# octave-fuzz.net
KiCad netlist of a schematic drawn in EAGLE
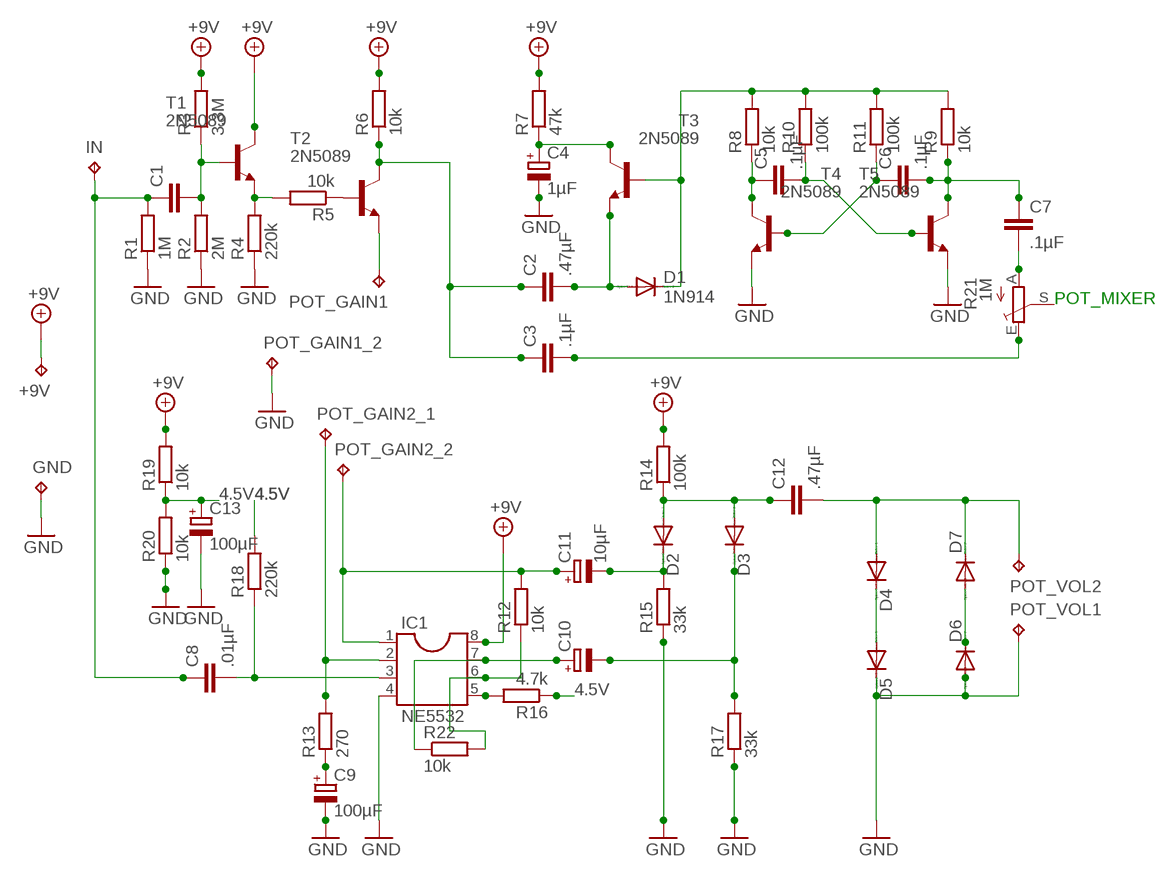
[diagram p0: schematic, sheet 1]

(export (version "E")
  (design (tool "Eeschema 10.0.6"))
  (components
    (comp (ref "+9V")
      (value "TPPAD1-20Y")
      (footprint "eagle-import:P1-20Y")
      (libsource (lib "eagle-import") (part "TPPAD1-20Y"))
    )
    (comp (ref "C1")
      (value "C-EU050-025X075")
      (footprint "eagle-import:C050-025X075")
      (libsource (lib "eagle-import") (part "C-EU050-025X075"))
    )
    (comp (ref "C2")
      (value ".47µF")
      (footprint "eagle-import:C050-025X075")
      (libsource (lib "eagle-import") (part "C-EU050-025X075"))
    )
    (comp (ref "C3")
      (value ".1µF")
      (footprint "eagle-import:C050-025X075")
      (libsource (lib "eagle-import") (part "C-EU050-025X075"))
    )
    (comp (ref "C4")
      (value "1µF")
      (footprint "eagle-import:E3,5-8")
      (libsource (lib "eagle-import") (part "CPOL-EUE3.5-8"))
    )
    (comp (ref "C5")
      (value ".1µF")
      (footprint "eagle-import:C050-025X075")
      (libsource (lib "eagle-import") (part "C-EU050-025X075"))
    )
    (comp (ref "C6")
      (value ".1µF")
      (footprint "eagle-import:C050-025X075")
      (libsource (lib "eagle-import") (part "C-EU050-025X075"))
    )
    (comp (ref "C7")
      (value ".1µF")
      (footprint "eagle-import:C050-025X075")
      (libsource (lib "eagle-import") (part "C-EU050-025X075"))
    )
    (comp (ref "C8")
      (value ".01µF")
      (footprint "eagle-import:C050-025X075")
      (libsource (lib "eagle-import") (part "C-EU050-025X075"))
    )
    (comp (ref "C9")
      (value "100µF")
      (footprint "eagle-import:E3,5-8")
      (libsource (lib "eagle-import") (part "CPOL-EUE3.5-8"))
    )
    (comp (ref "C10")
      (value "CPOL-EUE3.5-8")
      (footprint "eagle-import:E3,5-8")
      (libsource (lib "eagle-import") (part "CPOL-EUE3.5-8"))
    )
    (comp (ref "C11")
      (value "10µF")
      (footprint "eagle-import:E3,5-8")
      (libsource (lib "eagle-import") (part "CPOL-EUE3.5-8"))
    )
    (comp (ref "C12")
      (value ".47µF")
      (footprint "eagle-import:C050-025X075")
      (libsource (lib "eagle-import") (part "C-EU050-025X075"))
    )
    (comp (ref "C13")
      (value "100µF")
      (footprint "eagle-import:E3,5-8")
      (libsource (lib "eagle-import") (part "CPOL-EUE3.5-8"))
    )
    (comp (ref "D1")
      (value "1N914")
      (footprint "eagle-import:D-12.5")
      (libsource (lib "eagle-import") (part "DIODE-D-12.5"))
    )
    (comp (ref "D2")
      (value "DIODE-D-12.5")
      (footprint "eagle-import:D-12.5")
      (libsource (lib "eagle-import") (part "DIODE-D-12.5"))
    )
    (comp (ref "D3")
      (value "DIODE-D-12.5")
      (footprint "eagle-import:D-12.5")
      (libsource (lib "eagle-import") (part "DIODE-D-12.5"))
    )
    (comp (ref "D4")
      (value "DIODE-D-12.5")
      (footprint "eagle-import:D-12.5")
      (libsource (lib "eagle-import") (part "DIODE-D-12.5"))
    )
    (comp (ref "D5")
      (value "DIODE-D-12.5")
      (footprint "eagle-import:D-12.5")
      (libsource (lib "eagle-import") (part "DIODE-D-12.5"))
    )
    (comp (ref "D6")
      (value "DIODE-D-12.5")
      (footprint "eagle-import:D-12.5")
      (libsource (lib "eagle-import") (part "DIODE-D-12.5"))
    )
    (comp (ref "D7")
      (value "DIODE-D-12.5")
      (footprint "eagle-import:D-12.5")
      (libsource (lib "eagle-import") (part "DIODE-D-12.5"))
    )
    (comp (ref "GND")
      (value "TPPAD1-20Y")
      (footprint "eagle-import:P1-20Y")
      (libsource (lib "eagle-import") (part "TPPAD1-20Y"))
    )
    (comp (ref "IC1")
      (value "NE5532")
      (footprint "eagle-import:DIL08")
      (libsource (lib "eagle-import") (part "DIL8"))
    )
    (comp (ref "IN")
      (value "TPPAD1-17Y")
      (footprint "eagle-import:P1-17Y")
      (libsource (lib "eagle-import") (part "TPPAD1-17Y"))
    )
    (comp (ref "POT_GAIN1")
      (value "TPPAD1-20Y")
      (footprint "eagle-import:P1-20Y")
      (libsource (lib "eagle-import") (part "TPPAD1-20Y"))
    )
    (comp (ref "POT_GAIN1_2")
      (value "TPPAD1-20Y")
      (footprint "eagle-import:P1-20Y")
      (libsource (lib "eagle-import") (part "TPPAD1-20Y"))
    )
    (comp (ref "POT_GAIN2_1")
      (value "TPPAD1-20Y")
      (footprint "eagle-import:P1-20Y")
      (libsource (lib "eagle-import") (part "TPPAD1-20Y"))
    )
    (comp (ref "POT_GAIN2_2")
      (value "TPPAD1-20Y")
      (footprint "eagle-import:P1-20Y")
      (libsource (lib "eagle-import") (part "TPPAD1-20Y"))
    )
    (comp (ref "POT_VOL1")
      (value "TPPAD1-20Y")
      (footprint "eagle-import:P1-20Y")
      (libsource (lib "eagle-import") (part "TPPAD1-20Y"))
    )
    (comp (ref "POT_VOL2")
      (value "TPPAD1-20Y")
      (footprint "eagle-import:P1-20Y")
      (libsource (lib "eagle-import") (part "TPPAD1-20Y"))
    )
    (comp (ref "R1")
      (value "1M")
      (footprint "eagle-import:0207_10")
      (libsource (lib "eagle-import") (part "R-EU_0207/10"))
    )
    (comp (ref "R2")
      (value "2M")
      (footprint "eagle-import:0207_10")
      (libsource (lib "eagle-import") (part "R-EU_0207/10"))
    )
    (comp (ref "R3")
      (value "3.3M")
      (footprint "eagle-import:0207_10")
      (libsource (lib "eagle-import") (part "R-EU_0207/10"))
    )
    (comp (ref "R4")
      (value "220k")
      (footprint "eagle-import:0207_10")
      (libsource (lib "eagle-import") (part "R-EU_0207/10"))
    )
    (comp (ref "R5")
      (value "10k")
      (footprint "eagle-import:0207_10")
      (libsource (lib "eagle-import") (part "R-EU_0207/10"))
    )
    (comp (ref "R6")
      (value "10k")
      (footprint "eagle-import:0207_10")
      (libsource (lib "eagle-import") (part "R-EU_0207/10"))
    )
    (comp (ref "R7")
      (value "47k")
      (footprint "eagle-import:0207_10")
      (libsource (lib "eagle-import") (part "R-EU_0207/10"))
    )
    (comp (ref "R8")
      (value "10k")
      (footprint "eagle-import:0207_10")
      (libsource (lib "eagle-import") (part "R-EU_0207/10"))
    )
    (comp (ref "R9")
      (value "10k")
      (footprint "eagle-import:0207_10")
      (libsource (lib "eagle-import") (part "R-EU_0207/10"))
    )
    (comp (ref "R10")
      (value "100k")
      (footprint "eagle-import:0207_10")
      (libsource (lib "eagle-import") (part "R-EU_0207/10"))
    )
    (comp (ref "R11")
      (value "100k")
      (footprint "eagle-import:0207_10")
      (libsource (lib "eagle-import") (part "R-EU_0207/10"))
    )
    (comp (ref "R12")
      (value "10k")
      (footprint "eagle-import:0207_10")
      (libsource (lib "eagle-import") (part "R-EU_0207/10"))
    )
    (comp (ref "R13")
      (value "270")
      (footprint "eagle-import:0207_10")
      (libsource (lib "eagle-import") (part "R-EU_0207/10"))
    )
    (comp (ref "R14")
      (value "100k")
      (footprint "eagle-import:0207_10")
      (libsource (lib "eagle-import") (part "R-EU_0207/10"))
    )
    (comp (ref "R15")
      (value "33k")
      (footprint "eagle-import:0207_10")
      (libsource (lib "eagle-import") (part "R-EU_0207/10"))
    )
    (comp (ref "R16")
      (value "4.7k")
      (footprint "eagle-import:0207_10")
      (libsource (lib "eagle-import") (part "R-EU_0207/10"))
    )
    (comp (ref "R17")
      (value "33k")
      (footprint "eagle-import:0207_10")
      (libsource (lib "eagle-import") (part "R-EU_0207/10"))
    )
    (comp (ref "R18")
      (value "220k")
      (footprint "eagle-import:0207_10")
      (libsource (lib "eagle-import") (part "R-EU_0207/10"))
    )
    (comp (ref "R19")
      (value "10k")
      (footprint "eagle-import:0207_10")
      (libsource (lib "eagle-import") (part "R-EU_0207/10"))
    )
    (comp (ref "R20")
      (value "10k")
      (footprint "eagle-import:0207_10")
      (libsource (lib "eagle-import") (part "R-EU_0207/10"))
    )
    (comp (ref "R21")
      (value "1M")
      (footprint "eagle-import:CA9V")
      (libsource (lib "eagle-import") (part "TRIM_EU-CA9V"))
    )
    (comp (ref "R22")
      (value "10k")
      (footprint "eagle-import:0207_10")
      (libsource (lib "eagle-import") (part "R-EU_0207/10"))
    )
    (comp (ref "T1")
      (value "2N5089")
      (footprint "eagle-import:TO92")
      (libsource (lib "eagle-import") (part "2N5089"))
    )
    (comp (ref "T2")
      (value "2N5089")
      (footprint "eagle-import:TO92")
      (libsource (lib "eagle-import") (part "2N5089"))
    )
    (comp (ref "T3")
      (value "2N5089")
      (footprint "eagle-import:TO92")
      (libsource (lib "eagle-import") (part "2N5089"))
    )
    (comp (ref "T4")
      (value "2N5089")
      (footprint "eagle-import:TO92")
      (libsource (lib "eagle-import") (part "2N5089"))
    )
    (comp (ref "T5")
      (value "2N5089")
      (footprint "eagle-import:TO92")
      (libsource (lib "eagle-import") (part "2N5089"))
    )
  )
  (nets
    (net (code "1") (name "+9V") (class "Default")
      (node (ref "+9V") (pin "TP") (pinfunction "TP_TP") (pintype "input"))
      (node (ref "IC1") (pin "8") (pinfunction "8_8") (pintype "passive"))
      (node (ref "R14") (pin "2") (pinfunction "2_2") (pintype "passive"))
      (node (ref "R19") (pin "2") (pinfunction "2_2") (pintype "passive"))
      (node (ref "R3") (pin "2") (pinfunction "2_2") (pintype "passive"))
      (node (ref "R6") (pin "2") (pinfunction "2_2") (pintype "passive"))
      (node (ref "R7") (pin "2") (pinfunction "2_2") (pintype "passive"))
      (node (ref "T1") (pin "1") (pinfunction "C_1") (pintype "passive"))
    )
    (net (code "2") (name "/4.5V") (class "Default")
      (node (ref "C13") (pin "+") (pinfunction "+_+") (pintype "passive"))
      (node (ref "R16") (pin "1") (pinfunction "1_1") (pintype "passive"))
      (node (ref "R18") (pin "2") (pinfunction "2_2") (pintype "passive"))
      (node (ref "R19") (pin "1") (pinfunction "1_1") (pintype "passive"))
      (node (ref "R20") (pin "2") (pinfunction "2_2") (pintype "passive"))
    )
    (net (code "3") (name "GND") (class "Default")
      (node (ref "C13") (pin "-") (pinfunction "-_-") (pintype "passive"))
      (node (ref "C4") (pin "-") (pinfunction "-_-") (pintype "passive"))
      (node (ref "C9") (pin "-") (pinfunction "-_-") (pintype "passive"))
      (node (ref "D5") (pin "C") (pinfunction "C_C") (pintype "passive"))
      (node (ref "D6") (pin "A") (pinfunction "A_A") (pintype "passive"))
      (node (ref "GND") (pin "TP") (pinfunction "TP_TP") (pintype "input"))
      (node (ref "IC1") (pin "4") (pinfunction "4_4") (pintype "passive"))
      (node (ref "POT_GAIN1_2") (pin "TP") (pinfunction "TP_TP") (pintype "input"))
      (node (ref "POT_VOL1") (pin "TP") (pinfunction "TP_TP") (pintype "input"))
      (node (ref "R1") (pin "1") (pinfunction "1_1") (pintype "passive"))
      (node (ref "R15") (pin "1") (pinfunction "1_1") (pintype "passive"))
      (node (ref "R17") (pin "1") (pinfunction "1_1") (pintype "passive"))
      (node (ref "R2") (pin "1") (pinfunction "1_1") (pintype "passive"))
      (node (ref "R20") (pin "1") (pinfunction "1_1") (pintype "passive"))
      (node (ref "R4") (pin "1") (pinfunction "1_1") (pintype "passive"))
      (node (ref "T4") (pin "3") (pinfunction "E_3") (pintype "passive"))
      (node (ref "T5") (pin "3") (pinfunction "E_3") (pintype "passive"))
    )
    (net (code "4") (name "Net-(C1-Pad1)") (class "Default")
      (node (ref "C1") (pin "1") (pinfunction "1_1") (pintype "passive"))
      (node (ref "C8") (pin "1") (pinfunction "1_1") (pintype "passive"))
      (node (ref "IN") (pin "TP") (pinfunction "TP_TP") (pintype "input"))
      (node (ref "R1") (pin "2") (pinfunction "2_2") (pintype "passive"))
    )
    (net (code "5") (name "Net-(C3-Pad2)") (class "Default")
      (node (ref "C3") (pin "2") (pinfunction "2_2") (pintype "passive"))
      (node (ref "R21") (pin "E") (pinfunction "E_E") (pintype "passive"))
    )
    (net (code "6") (name "Net-(C7-Pad2)") (class "Default")
      (node (ref "C7") (pin "2") (pinfunction "2_2") (pintype "passive"))
      (node (ref "R21") (pin "A") (pinfunction "A_A") (pintype "passive"))
    )
    (net (code "7") (name "Net-(C8-Pad2)") (class "Default")
      (node (ref "C8") (pin "2") (pinfunction "2_2") (pintype "passive"))
      (node (ref "IC1") (pin "3") (pinfunction "3_3") (pintype "passive"))
      (node (ref "R18") (pin "1") (pinfunction "1_1") (pintype "passive"))
    )
    (net (code "8") (name "Net-(C9-Pad+)") (class "Default")
      (node (ref "C9") (pin "+") (pinfunction "+_+") (pintype "passive"))
      (node (ref "R13") (pin "1") (pinfunction "1_1") (pintype "passive"))
    )
    (net (code "9") (name "Net-(C10-Pad+)") (class "Default")
      (node (ref "C10") (pin "+") (pinfunction "+_+") (pintype "passive"))
      (node (ref "IC1") (pin "7") (pinfunction "7_7") (pintype "passive"))
      (node (ref "R22") (pin "1") (pinfunction "1_1") (pintype "passive"))
    )
    (net (code "10") (name "Net-(C10-Pad-)") (class "Default")
      (node (ref "C10") (pin "-") (pinfunction "-_-") (pintype "passive"))
      (node (ref "D3") (pin "C") (pinfunction "C_C") (pintype "passive"))
      (node (ref "R17") (pin "2") (pinfunction "2_2") (pintype "passive"))
    )
    (net (code "11") (name "Net-(C11-Pad+)") (class "Default")
      (node (ref "C11") (pin "+") (pinfunction "+_+") (pintype "passive"))
      (node (ref "IC1") (pin "1") (pinfunction "1_1") (pintype "passive"))
      (node (ref "POT_GAIN2_2") (pin "TP") (pinfunction "TP_TP") (pintype "input"))
      (node (ref "R12") (pin "2") (pinfunction "2_2") (pintype "passive"))
    )
    (net (code "12") (name "Net-(C11-Pad-)") (class "Default")
      (node (ref "C11") (pin "-") (pinfunction "-_-") (pintype "passive"))
      (node (ref "D2") (pin "C") (pinfunction "C_C") (pintype "passive"))
      (node (ref "R15") (pin "2") (pinfunction "2_2") (pintype "passive"))
    )
    (net (code "13") (name "Net-(C12-Pad1)") (class "Default")
      (node (ref "C12") (pin "1") (pinfunction "1_1") (pintype "passive"))
      (node (ref "D2") (pin "A") (pinfunction "A_A") (pintype "passive"))
      (node (ref "D3") (pin "A") (pinfunction "A_A") (pintype "passive"))
      (node (ref "R14") (pin "1") (pinfunction "1_1") (pintype "passive"))
    )
    (net (code "14") (name "Net-(C12-Pad2)") (class "Default")
      (node (ref "C12") (pin "2") (pinfunction "2_2") (pintype "passive"))
      (node (ref "D4") (pin "A") (pinfunction "A_A") (pintype "passive"))
      (node (ref "D7") (pin "C") (pinfunction "C_C") (pintype "passive"))
      (node (ref "POT_VOL2") (pin "TP") (pinfunction "TP_TP") (pintype "input"))
    )
    (net (code "15") (name "Net-(D4-PadC)") (class "Default")
      (node (ref "D4") (pin "C") (pinfunction "C_C") (pintype "passive"))
      (node (ref "D5") (pin "A") (pinfunction "A_A") (pintype "passive"))
    )
    (net (code "16") (name "Net-(D6-PadC)") (class "Default")
      (node (ref "D6") (pin "C") (pinfunction "C_C") (pintype "passive"))
      (node (ref "D7") (pin "A") (pinfunction "A_A") (pintype "passive"))
    )
    (net (code "17") (name "Net-(IC1-Pad2)") (class "Default")
      (node (ref "IC1") (pin "2") (pinfunction "2_2") (pintype "passive"))
      (node (ref "POT_GAIN2_1") (pin "TP") (pinfunction "TP_TP") (pintype "input"))
      (node (ref "R13") (pin "2") (pinfunction "2_2") (pintype "passive"))
    )
    (net (code "18") (name "Net-(IC1-Pad5)") (class "Default")
      (node (ref "IC1") (pin "5") (pinfunction "5_5") (pintype "passive"))
      (node (ref "R16") (pin "2") (pinfunction "2_2") (pintype "passive"))
    )
    (net (code "19") (name "Net-(IC1-Pad6)") (class "Default")
      (node (ref "IC1") (pin "6") (pinfunction "6_6") (pintype "passive"))
      (node (ref "R12") (pin "1") (pinfunction "1_1") (pintype "passive"))
      (node (ref "R22") (pin "2") (pinfunction "2_2") (pintype "passive"))
    )
    (net (code "20") (name "Net-(T1-B)") (class "Default")
      (node (ref "C1") (pin "2") (pinfunction "2_2") (pintype "passive"))
      (node (ref "R2") (pin "2") (pinfunction "2_2") (pintype "passive"))
      (node (ref "R3") (pin "1") (pinfunction "1_1") (pintype "passive"))
      (node (ref "T1") (pin "2") (pinfunction "B_2") (pintype "passive"))
    )
    (net (code "21") (name "Net-(T1-E)") (class "Default")
      (node (ref "R4") (pin "2") (pinfunction "2_2") (pintype "passive"))
      (node (ref "R5") (pin "2") (pinfunction "2_2") (pintype "passive"))
      (node (ref "T1") (pin "3") (pinfunction "E_3") (pintype "passive"))
    )
    (net (code "22") (name "Net-(T2-B)") (class "Default")
      (node (ref "R5") (pin "1") (pinfunction "1_1") (pintype "passive"))
      (node (ref "T2") (pin "2") (pinfunction "B_2") (pintype "passive"))
    )
    (net (code "23") (name "Net-(T2-C)") (class "Default")
      (node (ref "C2") (pin "1") (pinfunction "1_1") (pintype "passive"))
      (node (ref "C3") (pin "1") (pinfunction "1_1") (pintype "passive"))
      (node (ref "R6") (pin "1") (pinfunction "1_1") (pintype "passive"))
      (node (ref "T2") (pin "1") (pinfunction "C_1") (pintype "passive"))
    )
    (net (code "24") (name "Net-(T2-E)") (class "Default")
      (node (ref "POT_GAIN1") (pin "TP") (pinfunction "TP_TP") (pintype "input"))
      (node (ref "T2") (pin "3") (pinfunction "E_3") (pintype "passive"))
    )
    (net (code "25") (name "Net-(T3-B)") (class "Default")
      (node (ref "D1") (pin "C") (pinfunction "C_C") (pintype "passive"))
      (node (ref "R10") (pin "2") (pinfunction "2_2") (pintype "passive"))
      (node (ref "R11") (pin "2") (pinfunction "2_2") (pintype "passive"))
      (node (ref "R8") (pin "2") (pinfunction "2_2") (pintype "passive"))
      (node (ref "R9") (pin "2") (pinfunction "2_2") (pintype "passive"))
      (node (ref "T3") (pin "2") (pinfunction "B_2") (pintype "passive"))
    )
    (net (code "26") (name "Net-(T3-C)") (class "Default")
      (node (ref "C4") (pin "+") (pinfunction "+_+") (pintype "passive"))
      (node (ref "R7") (pin "1") (pinfunction "1_1") (pintype "passive"))
      (node (ref "T3") (pin "1") (pinfunction "C_1") (pintype "passive"))
    )
    (net (code "27") (name "Net-(T3-E)") (class "Default")
      (node (ref "C2") (pin "2") (pinfunction "2_2") (pintype "passive"))
      (node (ref "D1") (pin "A") (pinfunction "A_A") (pintype "passive"))
      (node (ref "T3") (pin "3") (pinfunction "E_3") (pintype "passive"))
    )
    (net (code "28") (name "Net-(T4-B)") (class "Default")
      (node (ref "C6") (pin "1") (pinfunction "1_1") (pintype "passive"))
      (node (ref "R11") (pin "1") (pinfunction "1_1") (pintype "passive"))
      (node (ref "T4") (pin "2") (pinfunction "B_2") (pintype "passive"))
    )
    (net (code "29") (name "Net-(T4-C)") (class "Default")
      (node (ref "C5") (pin "1") (pinfunction "1_1") (pintype "passive"))
      (node (ref "R8") (pin "1") (pinfunction "1_1") (pintype "passive"))
      (node (ref "T4") (pin "1") (pinfunction "C_1") (pintype "passive"))
    )
    (net (code "30") (name "Net-(T5-B)") (class "Default")
      (node (ref "C5") (pin "2") (pinfunction "2_2") (pintype "passive"))
      (node (ref "R10") (pin "1") (pinfunction "1_1") (pintype "passive"))
      (node (ref "T5") (pin "2") (pinfunction "B_2") (pintype "passive"))
    )
    (net (code "31") (name "Net-(T5-C)") (class "Default")
      (node (ref "C6") (pin "2") (pinfunction "2_2") (pintype "passive"))
      (node (ref "C7") (pin "1") (pinfunction "1_1") (pintype "passive"))
      (node (ref "R9") (pin "1") (pinfunction "1_1") (pintype "passive"))
      (node (ref "T5") (pin "1") (pinfunction "C_1") (pintype "passive"))
    )
    (net (code "32") (name "unconnected-(R21-PadS)") (class "Default")
      (node (ref "R21") (pin "S") (pinfunction "S_S") (pintype "passive"))
    )
  )
)
